# funkshield_v1.net
KiCad netlist of a schematic drawn in EAGLE
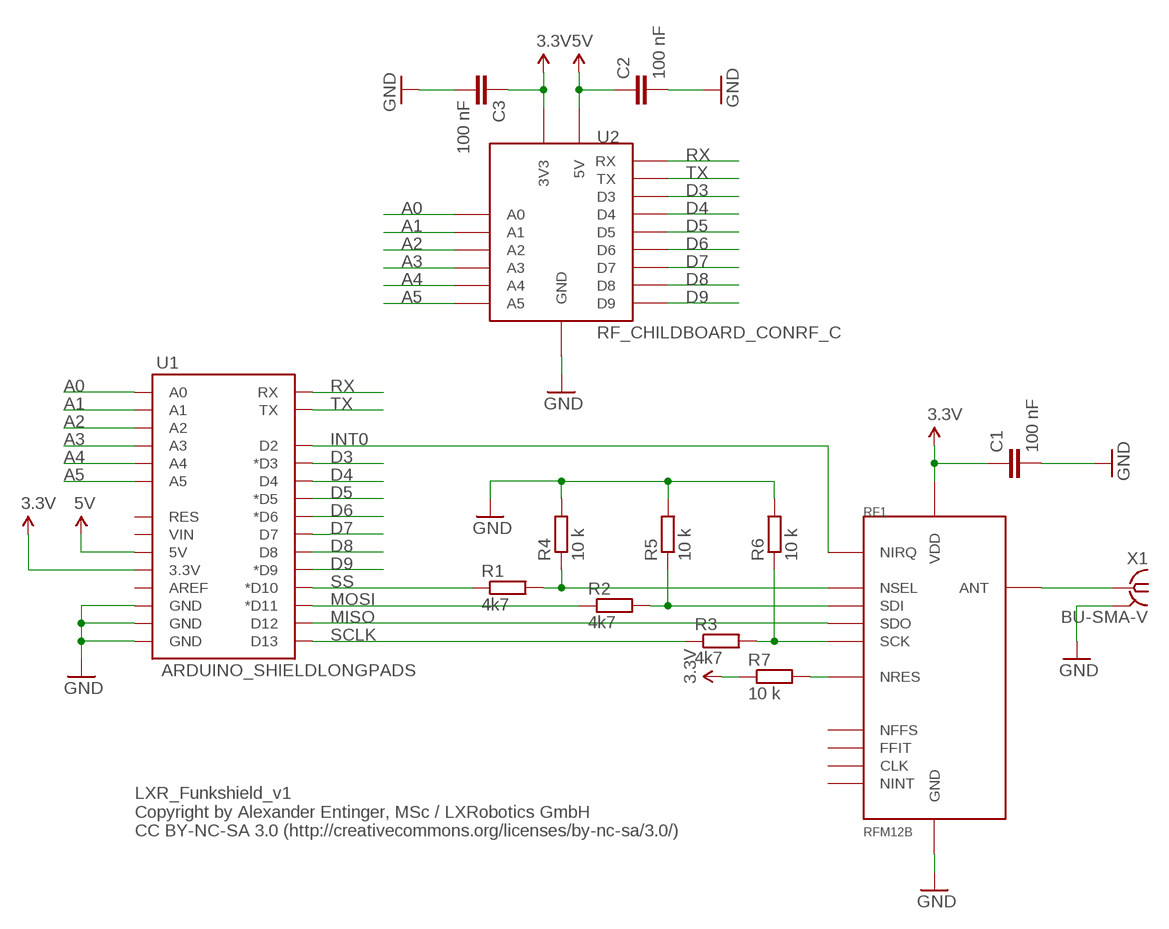
[diagram p0: schematic, sheet 1]

(export (version "E")
  (design (tool "Eeschema 10.0.6"))
  (components
    (comp (ref "C1")
      (value "100 nF")
      (footprint "eagle-import:C0805")
      (libsource (lib "eagle-import") (part "C-EUC0805"))
    )
    (comp (ref "C2")
      (value "100 nF")
      (footprint "eagle-import:C0805")
      (libsource (lib "eagle-import") (part "C-EUC0805"))
    )
    (comp (ref "C3")
      (value "100 nF")
      (footprint "eagle-import:C0805")
      (libsource (lib "eagle-import") (part "C-EUC0805"))
    )
    (comp (ref "R1")
      (value "4k7")
      (footprint "eagle-import:M0805")
      (libsource (lib "eagle-import") (part "R-EU_M0805"))
    )
    (comp (ref "R2")
      (value "4k7")
      (footprint "eagle-import:M0805")
      (libsource (lib "eagle-import") (part "R-EU_M0805"))
    )
    (comp (ref "R3")
      (value "4k7")
      (footprint "eagle-import:M0805")
      (libsource (lib "eagle-import") (part "R-EU_M0805"))
    )
    (comp (ref "R4")
      (value "10 k")
      (footprint "eagle-import:M0805")
      (libsource (lib "eagle-import") (part "R-EU_M0805"))
    )
    (comp (ref "R5")
      (value "10 k")
      (footprint "eagle-import:M0805")
      (libsource (lib "eagle-import") (part "R-EU_M0805"))
    )
    (comp (ref "R6")
      (value "10 k")
      (footprint "eagle-import:M0805")
      (libsource (lib "eagle-import") (part "R-EU_M0805"))
    )
    (comp (ref "R7")
      (value "10 k")
      (footprint "eagle-import:M0805")
      (libsource (lib "eagle-import") (part "R-EU_M0805"))
    )
    (comp (ref "RF1")
      (value "RFM12B")
      (footprint "eagle-import:RFM12B")
      (libsource (lib "eagle-import") (part "RFM12B"))
    )
    (comp (ref "U1")
      (value "ARDUINO_SHIELDLONGPADS")
      (footprint "eagle-import:DUEMILANOVE_SHIELD_LONGPADS")
      (libsource (lib "eagle-import") (part "ARDUINO_SHIELDLONGPADS"))
    )
    (comp (ref "U2")
      (value "RF_CHILDBOARD_CONRF_C")
      (footprint "eagle-import:RF_CHILDBOARD_CON")
      (libsource (lib "eagle-import") (part "RF_CHILDBOARD_CONRF_C"))
    )
    (comp (ref "X1")
      (value "BU-SMA-V")
      (footprint "eagle-import:BU-SMA-V")
      (libsource (lib "eagle-import") (part "BU-SMA-V"))
    )
  )
  (nets
    (net (code "1") (name "/A0") (class "Default")
      (node (ref "U1") (pin "A0") (pinfunction "A0_A0") (pintype "bidirectional"))
      (node (ref "U2") (pin "A0") (pinfunction "A0_A0") (pintype "bidirectional"))
    )
    (net (code "2") (name "/A1") (class "Default")
      (node (ref "U1") (pin "A1") (pinfunction "A1_A1") (pintype "bidirectional"))
      (node (ref "U2") (pin "A1") (pinfunction "A1_A1") (pintype "bidirectional"))
    )
    (net (code "3") (name "/A2") (class "Default")
      (node (ref "U1") (pin "A2") (pinfunction "A2_A2") (pintype "bidirectional"))
      (node (ref "U2") (pin "A2") (pinfunction "A2_A2") (pintype "bidirectional"))
    )
    (net (code "4") (name "/A3") (class "Default")
      (node (ref "U1") (pin "A3") (pinfunction "A3_A3") (pintype "bidirectional"))
      (node (ref "U2") (pin "A3") (pinfunction "A3_A3") (pintype "bidirectional"))
    )
    (net (code "5") (name "/A4") (class "Default")
      (node (ref "U1") (pin "A4") (pinfunction "A4_A4") (pintype "bidirectional"))
      (node (ref "U2") (pin "A4") (pinfunction "A4_A4") (pintype "bidirectional"))
    )
    (net (code "6") (name "/A5") (class "Default")
      (node (ref "U1") (pin "A5") (pinfunction "A5_A5") (pintype "bidirectional"))
      (node (ref "U2") (pin "A5") (pinfunction "A5_A5") (pintype "bidirectional"))
    )
    (net (code "7") (name "/D3") (class "Default")
      (node (ref "U1") (pin "D3") (pinfunction "*D3_D3") (pintype "bidirectional"))
      (node (ref "U2") (pin "D3") (pinfunction "D3_D3") (pintype "bidirectional"))
    )
    (net (code "8") (name "/D4") (class "Default")
      (node (ref "U1") (pin "D4") (pinfunction "D4_D4") (pintype "bidirectional"))
      (node (ref "U2") (pin "D4") (pinfunction "D4_D4") (pintype "bidirectional"))
    )
    (net (code "9") (name "/D5") (class "Default")
      (node (ref "U1") (pin "D5") (pinfunction "*D5_D5") (pintype "bidirectional"))
      (node (ref "U2") (pin "D5") (pinfunction "D5_D5") (pintype "bidirectional"))
    )
    (net (code "10") (name "/D6") (class "Default")
      (node (ref "U1") (pin "D6") (pinfunction "*D6_D6") (pintype "bidirectional"))
      (node (ref "U2") (pin "D6") (pinfunction "D6_D6") (pintype "bidirectional"))
    )
    (net (code "11") (name "/D7") (class "Default")
      (node (ref "U1") (pin "D7") (pinfunction "D7_D7") (pintype "bidirectional"))
      (node (ref "U2") (pin "D7") (pinfunction "D7_D7") (pintype "bidirectional"))
    )
    (net (code "12") (name "/D8") (class "Default")
      (node (ref "U1") (pin "D8") (pinfunction "D8_D8") (pintype "bidirectional"))
      (node (ref "U2") (pin "D8") (pinfunction "D8_D8") (pintype "bidirectional"))
    )
    (net (code "13") (name "/D9") (class "Default")
      (node (ref "U1") (pin "D9") (pinfunction "*D9_D9") (pintype "bidirectional"))
      (node (ref "U2") (pin "D9") (pinfunction "D9_D9") (pintype "bidirectional"))
    )
    (net (code "14") (name "/INT0") (class "Default")
      (node (ref "RF1") (pin "NIRQ") (pinfunction "NIRQ_NIRQ") (pintype "bidirectional"))
      (node (ref "U1") (pin "D2") (pinfunction "D2_D2") (pintype "bidirectional"))
    )
    (net (code "15") (name "/MISO") (class "Default")
      (node (ref "RF1") (pin "SDO") (pinfunction "SDO_SDO") (pintype "bidirectional"))
      (node (ref "U1") (pin "D12") (pinfunction "D12_D12") (pintype "bidirectional"))
    )
    (net (code "16") (name "/MOSI") (class "Default")
      (node (ref "R2") (pin "1") (pinfunction "1_1") (pintype "passive"))
      (node (ref "U1") (pin "D11") (pinfunction "*D11_D11") (pintype "bidirectional"))
    )
    (net (code "17") (name "/RX") (class "Default")
      (node (ref "U1") (pin "RX") (pinfunction "RX_RX") (pintype "bidirectional"))
      (node (ref "U2") (pin "RX") (pinfunction "RX_RX") (pintype "bidirectional"))
    )
    (net (code "18") (name "/SCLK") (class "Default")
      (node (ref "R3") (pin "1") (pinfunction "1_1") (pintype "passive"))
      (node (ref "U1") (pin "D13") (pinfunction "D13_D13") (pintype "bidirectional"))
    )
    (net (code "19") (name "/SS") (class "Default")
      (node (ref "R1") (pin "1") (pinfunction "1_1") (pintype "passive"))
      (node (ref "U1") (pin "D10") (pinfunction "*D10_D10") (pintype "bidirectional"))
    )
    (net (code "20") (name "/TX") (class "Default")
      (node (ref "U1") (pin "TX") (pinfunction "TX_TX") (pintype "bidirectional"))
      (node (ref "U2") (pin "TX") (pinfunction "TX_TX") (pintype "bidirectional"))
    )
    (net (code "21") (name "3.3V") (class "Default")
      (node (ref "C1") (pin "1") (pinfunction "1_1") (pintype "passive"))
      (node (ref "C3") (pin "1") (pinfunction "1_1") (pintype "passive"))
      (node (ref "R7") (pin "1") (pinfunction "1_1") (pintype "passive"))
      (node (ref "RF1") (pin "VDD") (pinfunction "VDD_VDD") (pintype "bidirectional"))
      (node (ref "U1") (pin "3.3V") (pinfunction "3.3V_3.3V") (pintype "bidirectional"))
      (node (ref "U2") (pin "3V3") (pinfunction "3V3_3V3") (pintype "bidirectional"))
    )
    (net (code "22") (name "5V") (class "Default")
      (node (ref "C2") (pin "1") (pinfunction "1_1") (pintype "passive"))
      (node (ref "U1") (pin "5V") (pinfunction "5V_5V") (pintype "bidirectional"))
      (node (ref "U2") (pin "5V") (pinfunction "5V_5V") (pintype "bidirectional"))
    )
    (net (code "23") (name "GND") (class "Default")
      (node (ref "C1") (pin "2") (pinfunction "2_2") (pintype "passive"))
      (node (ref "C2") (pin "2") (pinfunction "2_2") (pintype "passive"))
      (node (ref "C3") (pin "2") (pinfunction "2_2") (pintype "passive"))
      (node (ref "R4") (pin "2") (pinfunction "2_2") (pintype "passive"))
      (node (ref "R5") (pin "2") (pinfunction "2_2") (pintype "passive"))
      (node (ref "R6") (pin "2") (pinfunction "2_2") (pintype "passive"))
      (node (ref "RF1") (pin "GND") (pinfunction "GND_GND") (pintype "bidirectional"))
      (node (ref "RF1") (pin "GND1") (pinfunction "GND_GND1") (pintype "bidirectional"))
      (node (ref "U1") (pin "GND@0") (pinfunction "GND_GND@0") (pintype "bidirectional"))
      (node (ref "U1") (pin "GND@1") (pinfunction "GND_GND@1") (pintype "bidirectional"))
      (node (ref "U1") (pin "GND@2") (pinfunction "GND_GND@2") (pintype "bidirectional"))
      (node (ref "U2") (pin "GND") (pinfunction "GND_GND") (pintype "bidirectional"))
      (node (ref "U2") (pin "GND1") (pinfunction "GND_GND1") (pintype "bidirectional"))
      (node (ref "U2") (pin "GND2") (pinfunction "GND_GND2") (pintype "bidirectional"))
      (node (ref "X1") (pin "2") (pinfunction "GND_2") (pintype "power_in"))
    )
    (net (code "24") (name "Net-(R1-Pad2)") (class "Default")
      (node (ref "R1") (pin "2") (pinfunction "2_2") (pintype "passive"))
      (node (ref "R4") (pin "1") (pinfunction "1_1") (pintype "passive"))
      (node (ref "RF1") (pin "NSEL") (pinfunction "NSEL_NSEL") (pintype "bidirectional"))
    )
    (net (code "25") (name "Net-(R2-Pad2)") (class "Default")
      (node (ref "R2") (pin "2") (pinfunction "2_2") (pintype "passive"))
      (node (ref "R5") (pin "1") (pinfunction "1_1") (pintype "passive"))
      (node (ref "RF1") (pin "SDI") (pinfunction "SDI_SDI") (pintype "bidirectional"))
    )
    (net (code "26") (name "Net-(R3-Pad2)") (class "Default")
      (node (ref "R3") (pin "2") (pinfunction "2_2") (pintype "passive"))
      (node (ref "R6") (pin "1") (pinfunction "1_1") (pintype "passive"))
      (node (ref "RF1") (pin "SCK") (pinfunction "SCK_SCK") (pintype "bidirectional"))
    )
    (net (code "27") (name "Net-(R7-Pad2)") (class "Default")
      (node (ref "R7") (pin "2") (pinfunction "2_2") (pintype "passive"))
      (node (ref "RF1") (pin "NRES") (pinfunction "NRES_NRES") (pintype "bidirectional"))
    )
    (net (code "28") (name "Net-(RF1-PadANT)") (class "Default")
      (node (ref "RF1") (pin "ANT") (pinfunction "ANT_ANT") (pintype "bidirectional"))
      (node (ref "X1") (pin "1") (pinfunction "1_1") (pintype "passive"))
    )
    (net (code "29") (name "unconnected-(RF1-PadCLK)") (class "Default")
      (node (ref "RF1") (pin "CLK") (pinfunction "CLK_CLK") (pintype "bidirectional"))
    )
    (net (code "30") (name "unconnected-(RF1-PadFFIT)") (class "Default")
      (node (ref "RF1") (pin "FFIT") (pinfunction "FFIT_FFIT") (pintype "bidirectional"))
    )
    (net (code "31") (name "unconnected-(RF1-PadNFFS)") (class "Default")
      (node (ref "RF1") (pin "NFFS") (pinfunction "NFFS_NFFS") (pintype "bidirectional"))
    )
    (net (code "32") (name "unconnected-(RF1-PadNINT)") (class "Default")
      (node (ref "RF1") (pin "NINT") (pinfunction "NINT_NINT") (pintype "bidirectional"))
    )
    (net (code "33") (name "unconnected-(U1-PadAREF)") (class "Default")
      (node (ref "U1") (pin "AREF") (pinfunction "AREF_AREF") (pintype "bidirectional"))
    )
    (net (code "34") (name "unconnected-(U1-PadRES)") (class "Default")
      (node (ref "U1") (pin "RES") (pinfunction "RES_RES") (pintype "bidirectional"))
    )
    (net (code "35") (name "unconnected-(U1-PadVIN)") (class "Default")
      (node (ref "U1") (pin "VIN") (pinfunction "VIN_VIN") (pintype "bidirectional"))
    )
  )
)
